# Tilt-NE555-C.net
KiCad netlist of a schematic drawn in EAGLE
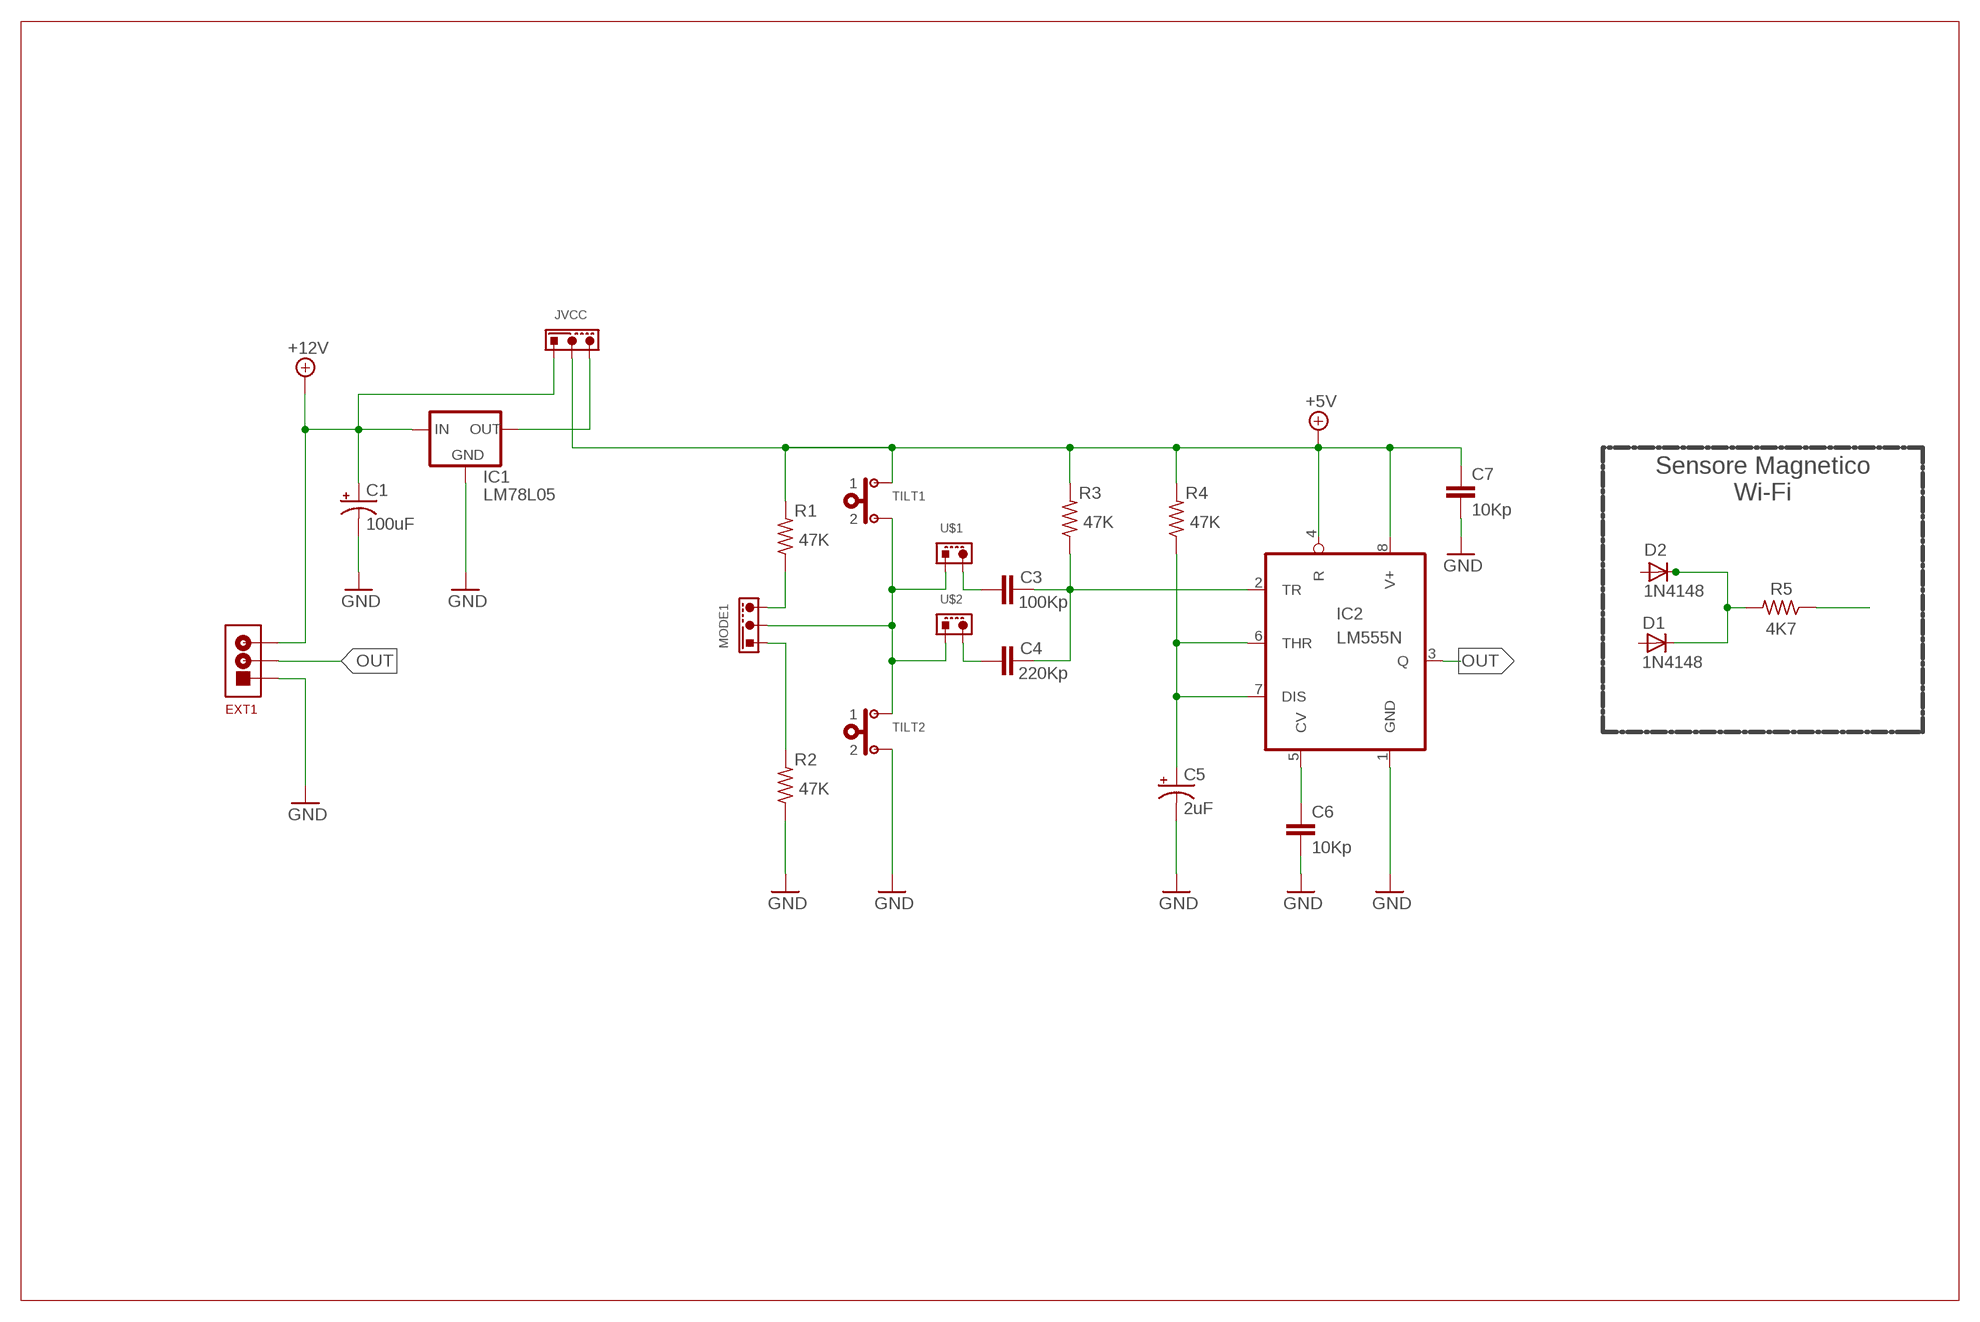
[diagram p0: schematic, sheet 1]

(export (version "E")
  (design (tool "Eeschema 10.0.6"))
  (components
    (comp (ref "C1")
      (value "100uF")
      (footprint "eagle-import:E5-5")
      (libsource (lib "eagle-import") (part "CPOL-USE5-5"))
    )
    (comp (ref "C3")
      (value "100Kp")
      (footprint "eagle-import:C075-032X103")
      (libsource (lib "eagle-import") (part "C-EU075-032X103"))
    )
    (comp (ref "C4")
      (value "220Kp")
      (footprint "eagle-import:C050-035X075")
      (libsource (lib "eagle-import") (part "C-EU050-035X075"))
    )
    (comp (ref "C5")
      (value "2uF")
      (footprint "eagle-import:E5-5")
      (libsource (lib "eagle-import") (part "CPOL-USE5-5"))
    )
    (comp (ref "C6")
      (value "10Kp")
      (footprint "eagle-import:C050-035X075")
      (libsource (lib "eagle-import") (part "C-EU050-035X075"))
    )
    (comp (ref "C7")
      (value "10Kp")
      (footprint "eagle-import:C050-035X075")
      (libsource (lib "eagle-import") (part "C-EU050-035X075"))
    )
    (comp (ref "D1")
      (value "1N4148")
      (footprint "eagle-import:DO35-10")
      (libsource (lib "eagle-import") (part "1N4148DO35-10"))
    )
    (comp (ref "D2")
      (value "1N4148")
      (footprint "eagle-import:DO35-10")
      (libsource (lib "eagle-import") (part "1N4148DO35-10"))
    )
    (comp (ref "EXT1")
      (value "MAMMUTH03")
      (footprint "eagle-import:MAMMUTH03")
      (libsource (lib "eagle-import") (part "MAMMUTH03"))
    )
    (comp (ref "IC1")
      (value "LM78L05")
      (footprint "eagle-import:78LXX")
      (libsource (lib "eagle-import") (part "78LXX"))
    )
    (comp (ref "IC2")
      (value "LM555N")
      (footprint "eagle-import:DIL08")
      (libsource (lib "eagle-import") (part "555NLM"))
    )
    (comp (ref "JVCC")
      (value "JUMPER3")
      (footprint "eagle-import:SIP03")
      (libsource (lib "eagle-import") (part "JUMPER3"))
    )
    (comp (ref "MODE1")
      (value "JUMPER3")
      (footprint "eagle-import:SIP03")
      (libsource (lib "eagle-import") (part "JUMPER3"))
    )
    (comp (ref "R1")
      (value "47K")
      (footprint "eagle-import:0207_15")
      (libsource (lib "eagle-import") (part "R-US_0207/15"))
    )
    (comp (ref "R2")
      (value "47K")
      (footprint "eagle-import:0207_15")
      (libsource (lib "eagle-import") (part "R-US_0207/15"))
    )
    (comp (ref "R3")
      (value "47K")
      (footprint "eagle-import:0207_15")
      (libsource (lib "eagle-import") (part "R-US_0207/15"))
    )
    (comp (ref "R4")
      (value "47K")
      (footprint "eagle-import:0207_15")
      (libsource (lib "eagle-import") (part "R-US_0207/15"))
    )
    (comp (ref "R5")
      (value "4K7")
      (footprint "eagle-import:0207_12")
      (libsource (lib "eagle-import") (part "R-US_0207/12"))
    )
    (comp (ref "TILT1")
      (value "PULSANTENO")
      (footprint "eagle-import:SIP02")
      (libsource (lib "eagle-import") (part "PULSANTENO"))
    )
    (comp (ref "TILT2")
      (value "PULSANTENO")
      (footprint "eagle-import:SIP02")
      (libsource (lib "eagle-import") (part "PULSANTENO"))
    )
    (comp (ref "U$1")
      (value "JUMPER2X1")
      (footprint "eagle-import:SIP02")
      (libsource (lib "eagle-import") (part "JUMPER2X1"))
    )
    (comp (ref "U$2")
      (value "JUMPER2X1")
      (footprint "eagle-import:SIP02")
      (libsource (lib "eagle-import") (part "JUMPER2X1"))
    )
  )
  (nets
    (net (code "1") (name "+5V") (class "Default")
      (node (ref "C7") (pin "1") (pinfunction "1_1") (pintype "passive"))
      (node (ref "IC2") (pin "4") (pinfunction "R_4") (pintype "input"))
      (node (ref "IC2") (pin "8") (pinfunction "V+_8") (pintype "power_in"))
      (node (ref "JVCC") (pin "1") (pinfunction "2_1") (pintype "bidirectional"))
      (node (ref "R1") (pin "2") (pinfunction "2_2") (pintype "passive"))
      (node (ref "R3") (pin "2") (pinfunction "2_2") (pintype "passive"))
      (node (ref "R4") (pin "2") (pinfunction "2_2") (pintype "passive"))
      (node (ref "TILT1") (pin "1") (pinfunction "1_1") (pintype "bidirectional"))
    )
    (net (code "2") (name "+12V") (class "Default")
      (node (ref "C1") (pin "+") (pinfunction "+_+") (pintype "passive"))
      (node (ref "EXT1") (pin "P$3") (pinfunction "3_P$3") (pintype "bidirectional"))
      (node (ref "IC1") (pin "IN") (pinfunction "IN_IN") (pintype "input"))
      (node (ref "JVCC") (pin "2") (pinfunction "1_2") (pintype "bidirectional"))
    )
    (net (code "3") (name "GND") (class "Default")
      (node (ref "C1") (pin "-") (pinfunction "-_-") (pintype "passive"))
      (node (ref "C5") (pin "-") (pinfunction "-_-") (pintype "passive"))
      (node (ref "C6") (pin "2") (pinfunction "2_2") (pintype "passive"))
      (node (ref "C7") (pin "2") (pinfunction "2_2") (pintype "passive"))
      (node (ref "EXT1") (pin "P$1") (pinfunction "1_P$1") (pintype "bidirectional"))
      (node (ref "IC1") (pin "GND") (pinfunction "GND_GND") (pintype "input"))
      (node (ref "IC2") (pin "1") (pinfunction "GND_1") (pintype "power_in"))
      (node (ref "R2") (pin "1") (pinfunction "1_1") (pintype "passive"))
      (node (ref "TILT2") (pin "2") (pinfunction "2_2") (pintype "bidirectional"))
    )
    (net (code "4") (name "Net-(C3-Pad1)") (class "Default")
      (node (ref "C3") (pin "1") (pinfunction "1_1") (pintype "passive"))
      (node (ref "U$1") (pin "2") (pinfunction "2_2") (pintype "bidirectional"))
    )
    (net (code "5") (name "Net-(C4-Pad1)") (class "Default")
      (node (ref "C4") (pin "1") (pinfunction "1_1") (pintype "passive"))
      (node (ref "U$2") (pin "2") (pinfunction "2_2") (pintype "bidirectional"))
    )
    (net (code "6") (name "Net-(D1-PadC)") (class "Default")
      (node (ref "D1") (pin "C") (pinfunction "C_C") (pintype "passive"))
      (node (ref "D2") (pin "C") (pinfunction "C_C") (pintype "passive"))
      (node (ref "R5") (pin "2") (pinfunction "2_2") (pintype "passive"))
    )
    (net (code "7") (name "Net-(IC1-PadOUT)") (class "Default")
      (node (ref "IC1") (pin "OUT") (pinfunction "OUT_OUT") (pintype "passive"))
      (node (ref "JVCC") (pin "3") (pinfunction "3_3") (pintype "bidirectional"))
    )
    (net (code "8") (name "Net-(IC2-CV)") (class "Default")
      (node (ref "C6") (pin "1") (pinfunction "1_1") (pintype "passive"))
      (node (ref "IC2") (pin "5") (pinfunction "CV_5") (pintype "input"))
    )
    (net (code "9") (name "Net-(IC2-DIS)") (class "Default")
      (node (ref "C5") (pin "+") (pinfunction "+_+") (pintype "passive"))
      (node (ref "IC2") (pin "6") (pinfunction "THR_6") (pintype "input"))
      (node (ref "IC2") (pin "7") (pinfunction "DIS_7") (pintype "input"))
      (node (ref "R4") (pin "1") (pinfunction "1_1") (pintype "passive"))
    )
    (net (code "10") (name "Net-(IC2-TR)") (class "Default")
      (node (ref "C3") (pin "2") (pinfunction "2_2") (pintype "passive"))
      (node (ref "C4") (pin "2") (pinfunction "2_2") (pintype "passive"))
      (node (ref "IC2") (pin "2") (pinfunction "TR_2") (pintype "input"))
      (node (ref "R3") (pin "1") (pinfunction "1_1") (pintype "passive"))
    )
    (net (code "11") (name "Net-(MODE1-1)") (class "Default")
      (node (ref "MODE1") (pin "2") (pinfunction "1_2") (pintype "bidirectional"))
      (node (ref "R2") (pin "2") (pinfunction "2_2") (pintype "passive"))
    )
    (net (code "12") (name "Net-(MODE1-2)") (class "Default")
      (node (ref "MODE1") (pin "1") (pinfunction "2_1") (pintype "bidirectional"))
      (node (ref "TILT1") (pin "2") (pinfunction "2_2") (pintype "bidirectional"))
      (node (ref "TILT2") (pin "1") (pinfunction "1_1") (pintype "bidirectional"))
      (node (ref "U$1") (pin "1") (pinfunction "1_1") (pintype "bidirectional"))
      (node (ref "U$2") (pin "1") (pinfunction "1_1") (pintype "bidirectional"))
    )
    (net (code "13") (name "Net-(MODE1-Pad3)") (class "Default")
      (node (ref "MODE1") (pin "3") (pinfunction "3_3") (pintype "bidirectional"))
      (node (ref "R1") (pin "1") (pinfunction "1_1") (pintype "passive"))
    )
    (net (code "14") (name "OUT") (class "Default")
      (node (ref "EXT1") (pin "P$2") (pinfunction "2_P$2") (pintype "bidirectional"))
      (node (ref "IC2") (pin "3") (pinfunction "Q_3") (pintype "output"))
    )
    (net (code "15") (name "unconnected-(D1-PadA)") (class "Default")
      (node (ref "D1") (pin "A") (pinfunction "A_A") (pintype "passive"))
    )
    (net (code "16") (name "unconnected-(D2-PadA)") (class "Default")
      (node (ref "D2") (pin "A") (pinfunction "A_A") (pintype "passive"))
    )
    (net (code "17") (name "unconnected-(R5-Pad1)") (class "Default")
      (node (ref "R5") (pin "1") (pinfunction "1_1") (pintype "passive"))
    )
  )
)
